# ADC_LED_Monitor.net
KiCad netlist of a schematic drawn in Altium Designer
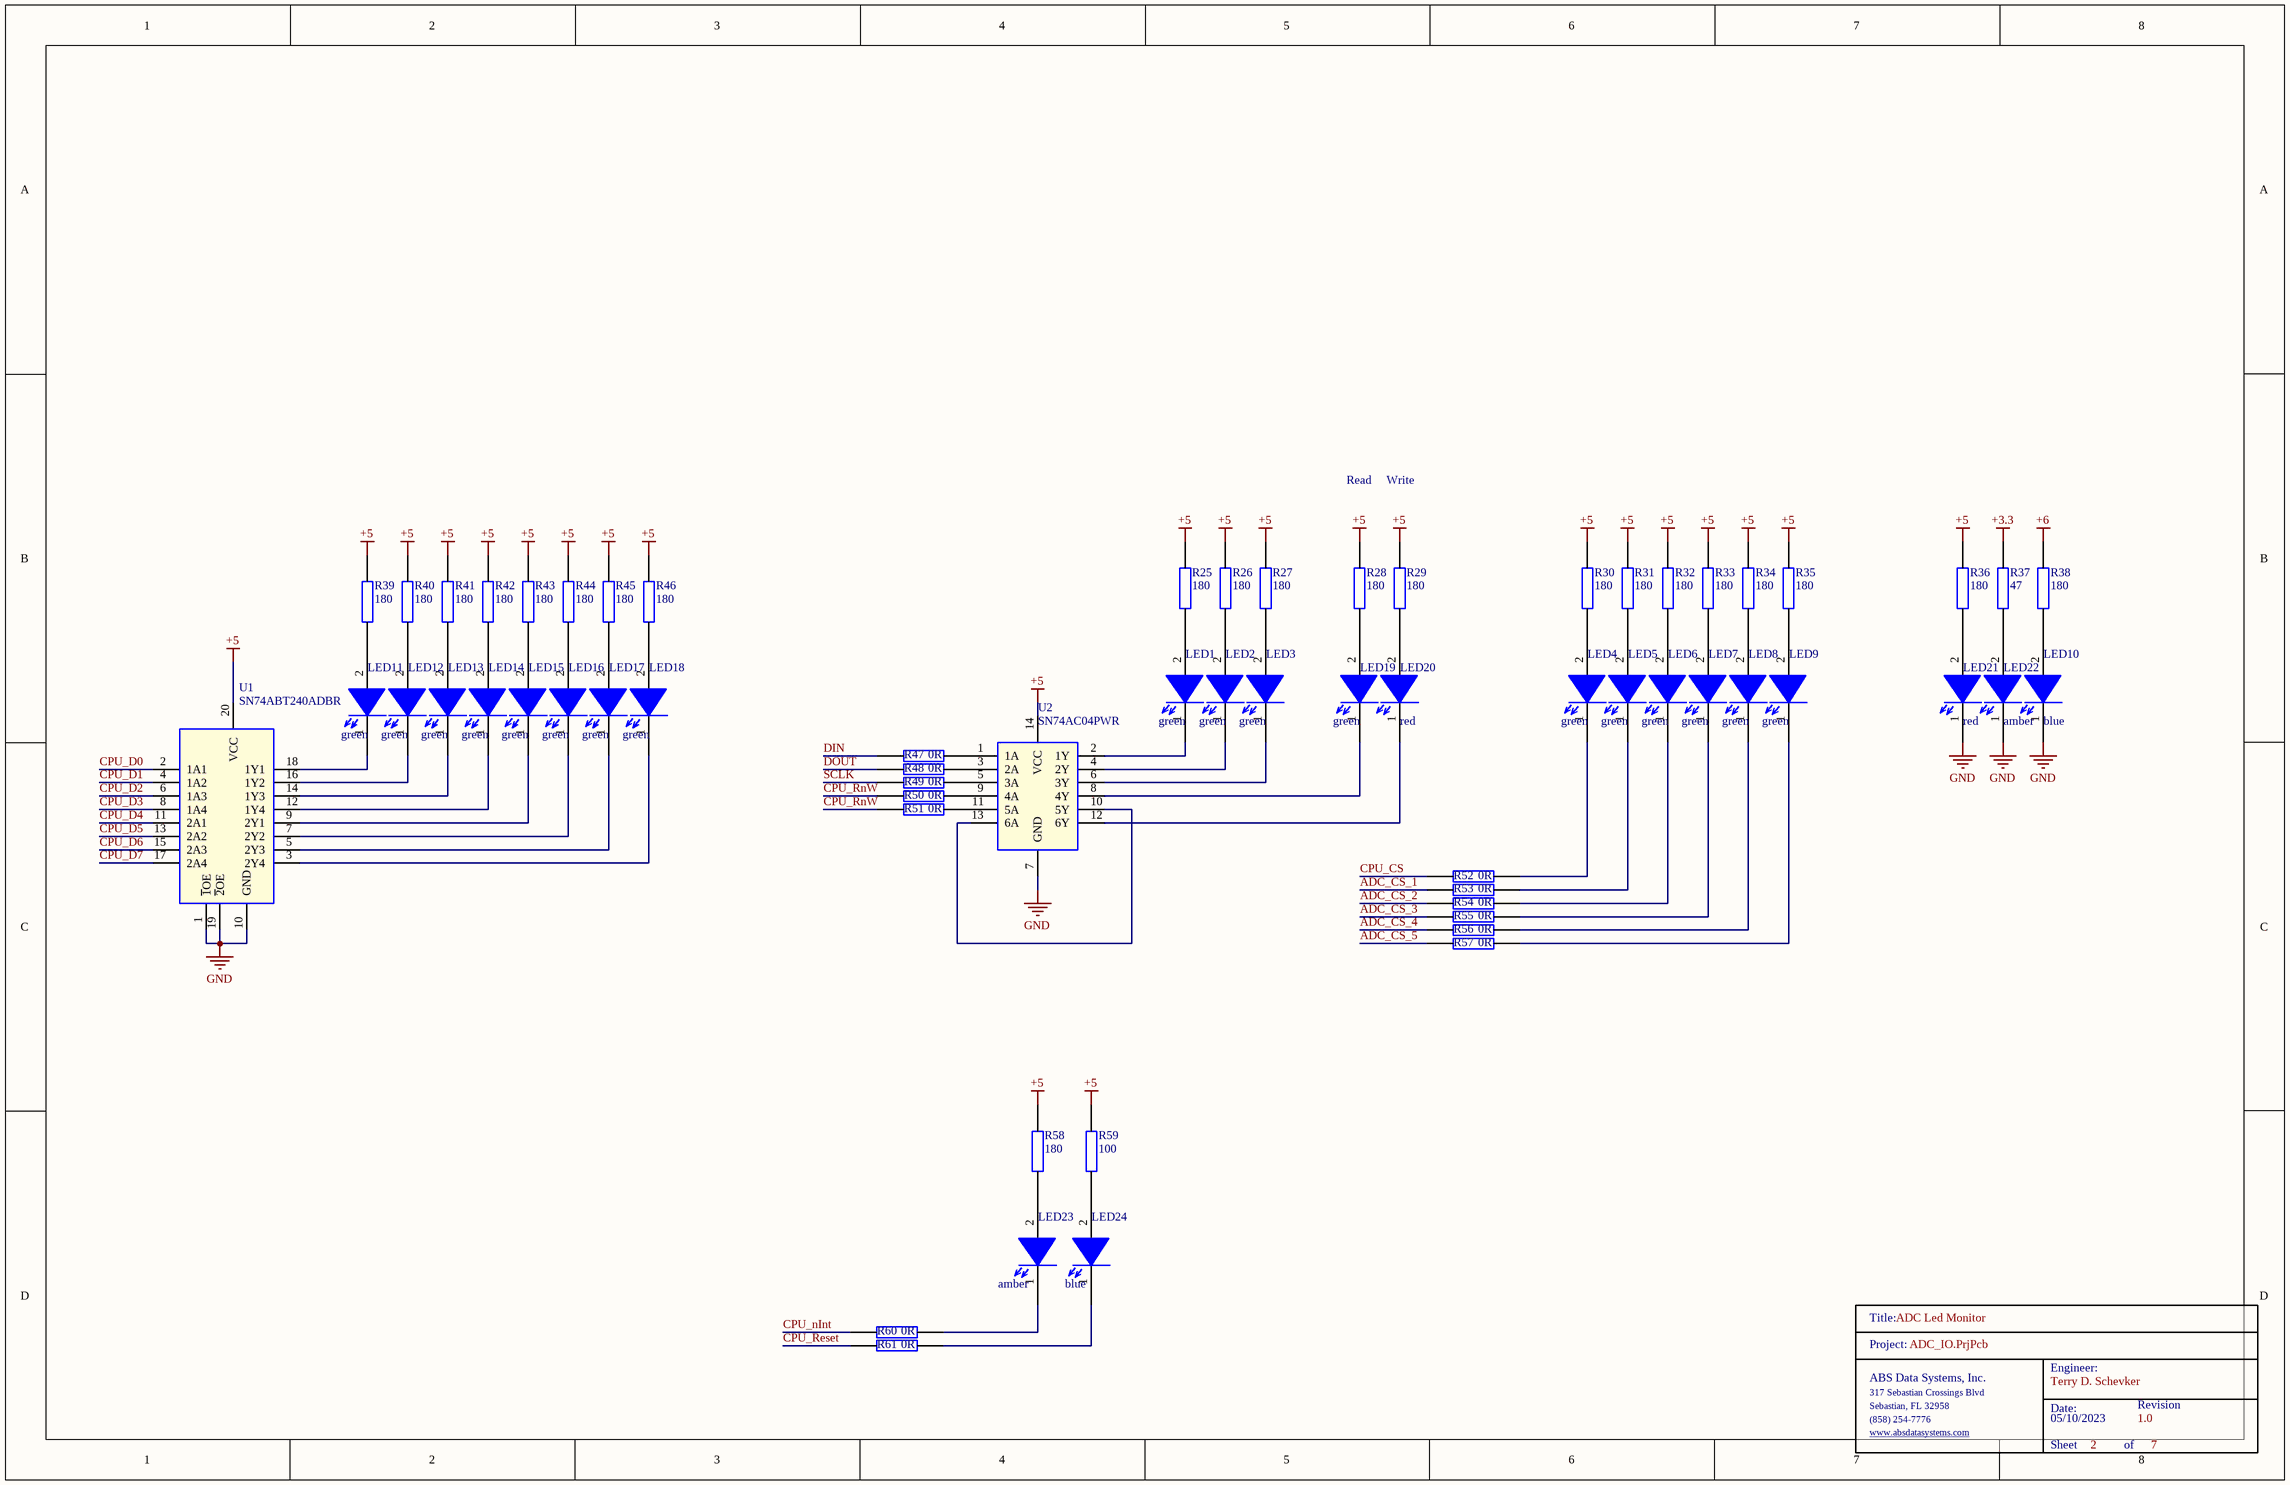
[diagram p0: ADC_LED_Monitor.SchDoc]

(export (version "E")
  (design (tool "Eeschema 10.0.6"))
  (components
    (comp (ref "LED1")
      (value "green")
      (footprint "0603_Diode")
      (description "Wurth Elektronik 0603 green")
      (fields
        (field (name "MANUFACTURER") "Wurth Electronics")
        (field (name "MANUFACTURER PART NUMBER") "150060GS75000")
      )
      (libsource (lib "Misc") (part "150060GS75000"))
    )
    (comp (ref "LED2")
      (value "green")
      (footprint "0603_Diode")
      (description "Wurth Elektronik 0603 green")
      (fields
        (field (name "MANUFACTURER") "Wurth Electronics")
        (field (name "MANUFACTURER PART NUMBER") "150060GS75000")
      )
      (libsource (lib "Misc") (part "150060GS75000"))
    )
    (comp (ref "LED3")
      (value "green")
      (footprint "0603_Diode")
      (description "Wurth Elektronik 0603 green")
      (fields
        (field (name "MANUFACTURER") "Wurth Electronics")
        (field (name "MANUFACTURER PART NUMBER") "150060GS75000")
      )
      (libsource (lib "Misc") (part "150060GS75000"))
    )
    (comp (ref "LED4")
      (value "green")
      (footprint "0603_Diode")
      (description "Wurth Elektronik 0603 green")
      (fields
        (field (name "MANUFACTURER") "Wurth Electronics")
        (field (name "MANUFACTURER PART NUMBER") "150060GS75000")
      )
      (libsource (lib "Misc") (part "150060GS75000"))
    )
    (comp (ref "LED5")
      (value "green")
      (footprint "0603_Diode")
      (description "Wurth Elektronik 0603 green")
      (fields
        (field (name "MANUFACTURER") "Wurth Electronics")
        (field (name "MANUFACTURER PART NUMBER") "150060GS75000")
      )
      (libsource (lib "Misc") (part "150060GS75000"))
    )
    (comp (ref "LED6")
      (value "green")
      (footprint "0603_Diode")
      (description "Wurth Elektronik 0603 green")
      (fields
        (field (name "MANUFACTURER") "Wurth Electronics")
        (field (name "MANUFACTURER PART NUMBER") "150060GS75000")
      )
      (libsource (lib "Misc") (part "150060GS75000"))
    )
    (comp (ref "LED7")
      (value "green")
      (footprint "0603_Diode")
      (description "Wurth Elektronik 0603 green")
      (fields
        (field (name "MANUFACTURER") "Wurth Electronics")
        (field (name "MANUFACTURER PART NUMBER") "150060GS75000")
      )
      (libsource (lib "Misc") (part "150060GS75000"))
    )
    (comp (ref "LED8")
      (value "green")
      (footprint "0603_Diode")
      (description "Wurth Elektronik 0603 green")
      (fields
        (field (name "MANUFACTURER") "Wurth Electronics")
        (field (name "MANUFACTURER PART NUMBER") "150060GS75000")
      )
      (libsource (lib "Misc") (part "150060GS75000"))
    )
    (comp (ref "LED9")
      (value "green")
      (footprint "0603_Diode")
      (description "Wurth Elektronik 0603 green")
      (fields
        (field (name "MANUFACTURER") "Wurth Electronics")
        (field (name "MANUFACTURER PART NUMBER") "150060GS75000")
      )
      (libsource (lib "Misc") (part "150060GS75000"))
    )
    (comp (ref "LED10")
      (value "blue")
      (footprint "0603_Diode")
      (description "Wurth Elektronik 0603 blue")
      (fields
        (field (name "MANUFACTURER") "Wurth Electronics")
        (field (name "MANUFACTURER PART NUMBER") "150060GS75000")
      )
      (libsource (lib "Misc") (part "150060BS75000"))
    )
    (comp (ref "LED11")
      (value "green")
      (footprint "0603_Diode")
      (description "Wurth Elektronik 0603 green")
      (fields
        (field (name "MANUFACTURER") "Wurth Electronics")
        (field (name "MANUFACTURER PART NUMBER") "150060GS75000")
      )
      (libsource (lib "Misc") (part "150060GS75000"))
    )
    (comp (ref "LED12")
      (value "green")
      (footprint "0603_Diode")
      (description "Wurth Elektronik 0603 green")
      (fields
        (field (name "MANUFACTURER") "Wurth Electronics")
        (field (name "MANUFACTURER PART NUMBER") "150060GS75000")
      )
      (libsource (lib "Misc") (part "150060GS75000"))
    )
    (comp (ref "LED13")
      (value "green")
      (footprint "0603_Diode")
      (description "Wurth Elektronik 0603 green")
      (fields
        (field (name "MANUFACTURER") "Wurth Electronics")
        (field (name "MANUFACTURER PART NUMBER") "150060GS75000")
      )
      (libsource (lib "Misc") (part "150060GS75000"))
    )
    (comp (ref "LED14")
      (value "green")
      (footprint "0603_Diode")
      (description "Wurth Elektronik 0603 green")
      (fields
        (field (name "MANUFACTURER") "Wurth Electronics")
        (field (name "MANUFACTURER PART NUMBER") "150060GS75000")
      )
      (libsource (lib "Misc") (part "150060GS75000"))
    )
    (comp (ref "LED15")
      (value "green")
      (footprint "0603_Diode")
      (description "Wurth Elektronik 0603 green")
      (fields
        (field (name "MANUFACTURER") "Wurth Electronics")
        (field (name "MANUFACTURER PART NUMBER") "150060GS75000")
      )
      (libsource (lib "Misc") (part "150060GS75000"))
    )
    (comp (ref "LED16")
      (value "green")
      (footprint "0603_Diode")
      (description "Wurth Elektronik 0603 green")
      (fields
        (field (name "MANUFACTURER") "Wurth Electronics")
        (field (name "MANUFACTURER PART NUMBER") "150060GS75000")
      )
      (libsource (lib "Misc") (part "150060GS75000"))
    )
    (comp (ref "LED17")
      (value "green")
      (footprint "0603_Diode")
      (description "Wurth Elektronik 0603 green")
      (fields
        (field (name "MANUFACTURER") "Wurth Electronics")
        (field (name "MANUFACTURER PART NUMBER") "150060GS75000")
      )
      (libsource (lib "Misc") (part "150060GS75000"))
    )
    (comp (ref "LED18")
      (value "green")
      (footprint "0603_Diode")
      (description "Wurth Elektronik 0603 green")
      (fields
        (field (name "MANUFACTURER") "Wurth Electronics")
        (field (name "MANUFACTURER PART NUMBER") "150060GS75000")
      )
      (libsource (lib "Misc") (part "150060GS75000"))
    )
    (comp (ref "LED19")
      (value "green")
      (footprint "0603_Diode")
      (description "Wurth Elektronik 0603 green")
      (fields
        (field (name "MANUFACTURER") "Wurth Electronics")
        (field (name "MANUFACTURER PART NUMBER") "150060GS75000")
      )
      (libsource (lib "Misc") (part "150060GS75000"))
    )
    (comp (ref "LED20")
      (value "red")
      (footprint "0603_Diode")
      (description "Wurth Elektronik 0603 red")
      (fields
        (field (name "MANUFACTURER") "Wurth Electronics")
        (field (name "MANUFACTURER PART NUMBER") "150060GS75000")
      )
      (libsource (lib "Misc") (part "150060RS75000"))
    )
    (comp (ref "LED21")
      (value "red")
      (footprint "0603_Diode")
      (description "Wurth Elektronik 0603 red")
      (fields
        (field (name "MANUFACTURER") "Wurth Electronics")
        (field (name "MANUFACTURER PART NUMBER") "150060GS75000")
      )
      (libsource (lib "Misc") (part "150060RS75000"))
    )
    (comp (ref "LED22")
      (value "amber")
      (footprint "0603_Diode")
      (description "Wurth Elektronik 0603 amber")
      (fields
        (field (name "MANUFACTURER") "Wurth Electronics")
        (field (name "MANUFACTURER PART NUMBER") "150060GS75000")
      )
      (libsource (lib "Misc") (part "150060AS75000"))
    )
    (comp (ref "LED23")
      (value "amber")
      (footprint "0603_Diode")
      (description "Wurth Elektronik 0603 amber")
      (fields
        (field (name "MANUFACTURER") "Wurth Electronics")
        (field (name "MANUFACTURER PART NUMBER") "150060GS75000")
      )
      (libsource (lib "Misc") (part "150060AS75000"))
    )
    (comp (ref "LED24")
      (value "blue")
      (footprint "0603_Diode")
      (description "Wurth Elektronik 0603 blue")
      (fields
        (field (name "MANUFACTURER") "Wurth Electronics")
        (field (name "MANUFACTURER PART NUMBER") "150060GS75000")
      )
      (libsource (lib "Misc") (part "150060BS75000"))
    )
    (comp (ref "R25")
      (value "180")
      (footprint "0603")
      (description "YAGEO 0603 180 ohm")
      (fields
        (field (name "MOUSER PART NUMBER") "603-RC0603JR-070RL")
        (field (name "MANUFACTURER_PART_NUMBER") "RC0603JR-070RL")
      )
      (libsource (lib "Resistors") (part "RC0603FR-13180RL"))
    )
    (comp (ref "R26")
      (value "180")
      (footprint "0603")
      (description "YAGEO 0603 180 ohm")
      (fields
        (field (name "MOUSER PART NUMBER") "603-RC0603JR-070RL")
        (field (name "MANUFACTURER_PART_NUMBER") "RC0603JR-070RL")
      )
      (libsource (lib "Resistors") (part "RC0603FR-13180RL"))
    )
    (comp (ref "R27")
      (value "180")
      (footprint "0603")
      (description "YAGEO 0603 180 ohm")
      (fields
        (field (name "MOUSER PART NUMBER") "603-RC0603JR-070RL")
        (field (name "MANUFACTURER_PART_NUMBER") "RC0603JR-070RL")
      )
      (libsource (lib "Resistors") (part "RC0603FR-13180RL"))
    )
    (comp (ref "R28")
      (value "180")
      (footprint "0603")
      (description "YAGEO 0603 180 ohm")
      (fields
        (field (name "MOUSER PART NUMBER") "603-RC0603JR-070RL")
        (field (name "MANUFACTURER_PART_NUMBER") "RC0603JR-070RL")
      )
      (libsource (lib "Resistors") (part "RC0603FR-13180RL"))
    )
    (comp (ref "R29")
      (value "180")
      (footprint "0603")
      (description "YAGEO 0603 180 ohm")
      (fields
        (field (name "MOUSER PART NUMBER") "603-RC0603JR-070RL")
        (field (name "MANUFACTURER_PART_NUMBER") "RC0603JR-070RL")
      )
      (libsource (lib "Resistors") (part "RC0603FR-13180RL"))
    )
    (comp (ref "R30")
      (value "180")
      (footprint "0603")
      (description "YAGEO 0603 180 ohm")
      (fields
        (field (name "MOUSER PART NUMBER") "603-RC0603JR-070RL")
        (field (name "MANUFACTURER_PART_NUMBER") "RC0603JR-070RL")
      )
      (libsource (lib "Resistors") (part "RC0603FR-13180RL"))
    )
    (comp (ref "R31")
      (value "180")
      (footprint "0603")
      (description "YAGEO 0603 180 ohm")
      (fields
        (field (name "MOUSER PART NUMBER") "603-RC0603JR-070RL")
        (field (name "MANUFACTURER_PART_NUMBER") "RC0603JR-070RL")
      )
      (libsource (lib "Resistors") (part "RC0603FR-13180RL"))
    )
    (comp (ref "R32")
      (value "180")
      (footprint "0603")
      (description "YAGEO 0603 180 ohm")
      (fields
        (field (name "MOUSER PART NUMBER") "603-RC0603JR-070RL")
        (field (name "MANUFACTURER_PART_NUMBER") "RC0603JR-070RL")
      )
      (libsource (lib "Resistors") (part "RC0603FR-13180RL"))
    )
    (comp (ref "R33")
      (value "180")
      (footprint "0603")
      (description "YAGEO 0603 180 ohm")
      (fields
        (field (name "MOUSER PART NUMBER") "603-RC0603JR-070RL")
        (field (name "MANUFACTURER_PART_NUMBER") "RC0603JR-070RL")
      )
      (libsource (lib "Resistors") (part "RC0603FR-13180RL"))
    )
    (comp (ref "R34")
      (value "180")
      (footprint "0603")
      (description "YAGEO 0603 180 ohm")
      (fields
        (field (name "MOUSER PART NUMBER") "603-RC0603JR-070RL")
        (field (name "MANUFACTURER_PART_NUMBER") "RC0603JR-070RL")
      )
      (libsource (lib "Resistors") (part "RC0603FR-13180RL"))
    )
    (comp (ref "R35")
      (value "180")
      (footprint "0603")
      (description "YAGEO 0603 180 ohm")
      (fields
        (field (name "MOUSER PART NUMBER") "603-RC0603JR-070RL")
        (field (name "MANUFACTURER_PART_NUMBER") "RC0603JR-070RL")
      )
      (libsource (lib "Resistors") (part "RC0603FR-13180RL"))
    )
    (comp (ref "R36")
      (value "180")
      (footprint "0603")
      (description "YAGEO 0603 180 ohm")
      (fields
        (field (name "MOUSER PART NUMBER") "603-RC0603JR-070RL")
        (field (name "MANUFACTURER_PART_NUMBER") "RC0603JR-070RL")
      )
      (libsource (lib "Resistors") (part "RC0603FR-13180RL"))
    )
    (comp (ref "R37")
      (value "47")
      (footprint "0603")
      (description "YAGEO 0603 47")
      (fields
        (field (name "MOUSER PART NUMBER") "603-RC0603JR-070RL")
        (field (name "MANUFACTURER_PART_NUMBER") "RC0603JR-070RL")
      )
      (libsource (lib "Resistors") (part "RC0603FR-0747KL"))
    )
    (comp (ref "R38")
      (value "180")
      (footprint "0603")
      (description "YAGEO 0603 180 ohm")
      (fields
        (field (name "MOUSER PART NUMBER") "603-RC0603JR-070RL")
        (field (name "MANUFACTURER_PART_NUMBER") "RC0603JR-070RL")
      )
      (libsource (lib "Resistors") (part "RC0603FR-13180RL"))
    )
    (comp (ref "R39")
      (value "180")
      (footprint "0603")
      (description "YAGEO 0603 180 ohm")
      (fields
        (field (name "MOUSER PART NUMBER") "603-RC0603JR-070RL")
        (field (name "MANUFACTURER_PART_NUMBER") "RC0603JR-070RL")
      )
      (libsource (lib "Resistors") (part "RC0603FR-13180RL"))
    )
    (comp (ref "R40")
      (value "180")
      (footprint "0603")
      (description "YAGEO 0603 180 ohm")
      (fields
        (field (name "MOUSER PART NUMBER") "603-RC0603JR-070RL")
        (field (name "MANUFACTURER_PART_NUMBER") "RC0603JR-070RL")
      )
      (libsource (lib "Resistors") (part "RC0603FR-13180RL"))
    )
    (comp (ref "R41")
      (value "180")
      (footprint "0603")
      (description "YAGEO 0603 180 ohm")
      (fields
        (field (name "MOUSER PART NUMBER") "603-RC0603JR-070RL")
        (field (name "MANUFACTURER_PART_NUMBER") "RC0603JR-070RL")
      )
      (libsource (lib "Resistors") (part "RC0603FR-13180RL"))
    )
    (comp (ref "R42")
      (value "180")
      (footprint "0603")
      (description "YAGEO 0603 180 ohm")
      (fields
        (field (name "MOUSER PART NUMBER") "603-RC0603JR-070RL")
        (field (name "MANUFACTURER_PART_NUMBER") "RC0603JR-070RL")
      )
      (libsource (lib "Resistors") (part "RC0603FR-13180RL"))
    )
    (comp (ref "R43")
      (value "180")
      (footprint "0603")
      (description "YAGEO 0603 180 ohm")
      (fields
        (field (name "MOUSER PART NUMBER") "603-RC0603JR-070RL")
        (field (name "MANUFACTURER_PART_NUMBER") "RC0603JR-070RL")
      )
      (libsource (lib "Resistors") (part "RC0603FR-13180RL"))
    )
    (comp (ref "R44")
      (value "180")
      (footprint "0603")
      (description "YAGEO 0603 180 ohm")
      (fields
        (field (name "MOUSER PART NUMBER") "603-RC0603JR-070RL")
        (field (name "MANUFACTURER_PART_NUMBER") "RC0603JR-070RL")
      )
      (libsource (lib "Resistors") (part "RC0603FR-13180RL"))
    )
    (comp (ref "R45")
      (value "180")
      (footprint "0603")
      (description "YAGEO 0603 180 ohm")
      (fields
        (field (name "MOUSER PART NUMBER") "603-RC0603JR-070RL")
        (field (name "MANUFACTURER_PART_NUMBER") "RC0603JR-070RL")
      )
      (libsource (lib "Resistors") (part "RC0603FR-13180RL"))
    )
    (comp (ref "R46")
      (value "180")
      (footprint "0603")
      (description "YAGEO 0603 180 ohm")
      (fields
        (field (name "MOUSER PART NUMBER") "603-RC0603JR-070RL")
        (field (name "MANUFACTURER_PART_NUMBER") "RC0603JR-070RL")
      )
      (libsource (lib "Resistors") (part "RC0603FR-13180RL"))
    )
    (comp (ref "R47")
      (value "0R")
      (footprint "0603")
      (description "YAGEO 0603 0 ohm")
      (fields
        (field (name "MOUSER PART NUMBER") "603-RC0603JR-070RL")
        (field (name "MANUFACTURER_PART_NUMBER") "RC0603JR-070RL")
      )
      (libsource (lib "Resistors") (part "RC0603JR-070RL"))
    )
    (comp (ref "R48")
      (value "0R")
      (footprint "0603")
      (description "YAGEO 0603 0 ohm")
      (fields
        (field (name "MOUSER PART NUMBER") "603-RC0603JR-070RL")
        (field (name "MANUFACTURER_PART_NUMBER") "RC0603JR-070RL")
      )
      (libsource (lib "Resistors") (part "RC0603JR-070RL"))
    )
    (comp (ref "R49")
      (value "0R")
      (footprint "0603")
      (description "YAGEO 0603 0 ohm")
      (fields
        (field (name "MOUSER PART NUMBER") "603-RC0603JR-070RL")
        (field (name "MANUFACTURER_PART_NUMBER") "RC0603JR-070RL")
      )
      (libsource (lib "Resistors") (part "RC0603JR-070RL"))
    )
    (comp (ref "R50")
      (value "0R")
      (footprint "0603")
      (description "YAGEO 0603 0 ohm")
      (fields
        (field (name "MOUSER PART NUMBER") "603-RC0603JR-070RL")
        (field (name "MANUFACTURER_PART_NUMBER") "RC0603JR-070RL")
      )
      (libsource (lib "Resistors") (part "RC0603JR-070RL"))
    )
    (comp (ref "R51")
      (value "0R")
      (footprint "0603")
      (description "YAGEO 0603 0 ohm")
      (fields
        (field (name "MOUSER PART NUMBER") "603-RC0603JR-070RL")
        (field (name "MANUFACTURER_PART_NUMBER") "RC0603JR-070RL")
      )
      (libsource (lib "Resistors") (part "RC0603JR-070RL"))
    )
    (comp (ref "R52")
      (value "0R")
      (footprint "0603")
      (description "YAGEO 0603 0 ohm")
      (fields
        (field (name "MOUSER PART NUMBER") "603-RC0603JR-070RL")
        (field (name "MANUFACTURER_PART_NUMBER") "RC0603JR-070RL")
      )
      (libsource (lib "Resistors") (part "RC0603JR-070RL"))
    )
    (comp (ref "R53")
      (value "0R")
      (footprint "0603")
      (description "YAGEO 0603 0 ohm")
      (fields
        (field (name "MOUSER PART NUMBER") "603-RC0603JR-070RL")
        (field (name "MANUFACTURER_PART_NUMBER") "RC0603JR-070RL")
      )
      (libsource (lib "Resistors") (part "RC0603JR-070RL"))
    )
    (comp (ref "R54")
      (value "0R")
      (footprint "0603")
      (description "YAGEO 0603 0 ohm")
      (fields
        (field (name "MOUSER PART NUMBER") "603-RC0603JR-070RL")
        (field (name "MANUFACTURER_PART_NUMBER") "RC0603JR-070RL")
      )
      (libsource (lib "Resistors") (part "RC0603JR-070RL"))
    )
    (comp (ref "R55")
      (value "0R")
      (footprint "0603")
      (description "YAGEO 0603 0 ohm")
      (fields
        (field (name "MOUSER PART NUMBER") "603-RC0603JR-070RL")
        (field (name "MANUFACTURER_PART_NUMBER") "RC0603JR-070RL")
      )
      (libsource (lib "Resistors") (part "RC0603JR-070RL"))
    )
    (comp (ref "R56")
      (value "0R")
      (footprint "0603")
      (description "YAGEO 0603 0 ohm")
      (fields
        (field (name "MOUSER PART NUMBER") "603-RC0603JR-070RL")
        (field (name "MANUFACTURER_PART_NUMBER") "RC0603JR-070RL")
      )
      (libsource (lib "Resistors") (part "RC0603JR-070RL"))
    )
    (comp (ref "R57")
      (value "0R")
      (footprint "0603")
      (description "YAGEO 0603 0 ohm")
      (fields
        (field (name "MOUSER PART NUMBER") "603-RC0603JR-070RL")
        (field (name "MANUFACTURER_PART_NUMBER") "RC0603JR-070RL")
      )
      (libsource (lib "Resistors") (part "RC0603JR-070RL"))
    )
    (comp (ref "R58")
      (value "180")
      (footprint "0603")
      (description "YAGEO 0603 180 ohm")
      (fields
        (field (name "MOUSER PART NUMBER") "603-RC0603JR-070RL")
        (field (name "MANUFACTURER_PART_NUMBER") "RC0603JR-070RL")
      )
      (libsource (lib "Resistors") (part "RC0603FR-13180RL"))
    )
    (comp (ref "R59")
      (value "100")
      (footprint "0603")
      (description "YAGEO 0603 100 ohm")
      (fields
        (field (name "MOUSER PART NUMBER") "603-RC0603JR-070RL")
        (field (name "MANUFACTURER_PART_NUMBER") "RC0603JR-070RL")
      )
      (libsource (lib "Resistors") (part "RC0603FR-10100RL"))
    )
    (comp (ref "R60")
      (value "0R")
      (footprint "0603")
      (description "YAGEO 0603 0 ohm")
      (fields
        (field (name "MOUSER PART NUMBER") "603-RC0603JR-070RL")
        (field (name "MANUFACTURER_PART_NUMBER") "RC0603JR-070RL")
      )
      (libsource (lib "Resistors") (part "RC0603JR-070RL"))
    )
    (comp (ref "R61")
      (value "0R")
      (footprint "0603")
      (description "YAGEO 0603 0 ohm")
      (fields
        (field (name "MOUSER PART NUMBER") "603-RC0603JR-070RL")
        (field (name "MANUFACTURER_PART_NUMBER") "RC0603JR-070RL")
      )
      (libsource (lib "Resistors") (part "RC0603JR-070RL"))
    )
    (comp (ref "TitleBlock_2") (value "TitleBlock") (libsource (lib "Misc") (part "TitleBlock")))
    (comp (ref "U1")
      (value "SN74ABT240ADBR")
      (footprint "SOP65P780X200-20N")
      (description "Octal Buffers/Drivers With 3-State Outputs")
      (fields (field (name "MOUSER PART NUMBER") "595-SN74ABT240ADBR"))
      (libsource (lib "Logic") (part "SN74ABT240ADBR"))
    )
    (comp (ref "U2")
      (value "SN74AC04PWR")
      (footprint "SOP65P640X120-14N")
      (description "Hex Inverters")
      (fields (field (name "MOUSER PART NUMBER") "595-SN74AC04PWR"))
      (libsource (lib "Logic") (part "SN74AC04PWR"))
    )
  )
  (nets
    (net (code "1") (name "+3.3") (class "Default")
      (node (ref "R37") (pin "1") (pinfunction "1_1") (pintype "passive"))
    )
    (net (code "2") (name "+5") (class "Default")
      (node (ref "R25") (pin "2") (pinfunction "2_2") (pintype "passive"))
      (node (ref "R26") (pin "2") (pinfunction "2_2") (pintype "passive"))
      (node (ref "R27") (pin "2") (pinfunction "2_2") (pintype "passive"))
      (node (ref "R28") (pin "2") (pinfunction "2_2") (pintype "passive"))
      (node (ref "R29") (pin "2") (pinfunction "2_2") (pintype "passive"))
      (node (ref "R30") (pin "2") (pinfunction "2_2") (pintype "passive"))
      (node (ref "R31") (pin "2") (pinfunction "2_2") (pintype "passive"))
      (node (ref "R32") (pin "2") (pinfunction "2_2") (pintype "passive"))
      (node (ref "R33") (pin "2") (pinfunction "2_2") (pintype "passive"))
      (node (ref "R34") (pin "2") (pinfunction "2_2") (pintype "passive"))
      (node (ref "R35") (pin "2") (pinfunction "2_2") (pintype "passive"))
      (node (ref "R36") (pin "2") (pinfunction "2_2") (pintype "passive"))
      (node (ref "R39") (pin "2") (pinfunction "2_2") (pintype "passive"))
      (node (ref "R40") (pin "2") (pinfunction "2_2") (pintype "passive"))
      (node (ref "R41") (pin "2") (pinfunction "2_2") (pintype "passive"))
      (node (ref "R42") (pin "2") (pinfunction "2_2") (pintype "passive"))
      (node (ref "R43") (pin "2") (pinfunction "2_2") (pintype "passive"))
      (node (ref "R44") (pin "2") (pinfunction "2_2") (pintype "passive"))
      (node (ref "R45") (pin "2") (pinfunction "2_2") (pintype "passive"))
      (node (ref "R46") (pin "2") (pinfunction "2_2") (pintype "passive"))
      (node (ref "R58") (pin "2") (pinfunction "2_2") (pintype "passive"))
      (node (ref "R59") (pin "1") (pinfunction "1_1") (pintype "passive"))
      (node (ref "U1") (pin "20") (pinfunction "VCC_20") (pintype "passive"))
      (node (ref "U2") (pin "14") (pinfunction "VCC_14") (pintype "passive"))
    )
    (net (code "3") (name "+6") (class "Default")
      (node (ref "R38") (pin "2") (pinfunction "2_2") (pintype "passive"))
    )
    (net (code "4") (name "/ADC_CS_1") (class "Default")
      (node (ref "R53") (pin "1") (pinfunction "1_1") (pintype "passive"))
    )
    (net (code "5") (name "/ADC_CS_2") (class "Default")
      (node (ref "R54") (pin "1") (pinfunction "1_1") (pintype "passive"))
    )
    (net (code "6") (name "/ADC_CS_3") (class "Default")
      (node (ref "R55") (pin "1") (pinfunction "1_1") (pintype "passive"))
    )
    (net (code "7") (name "/ADC_CS_4") (class "Default")
      (node (ref "R56") (pin "1") (pinfunction "1_1") (pintype "passive"))
    )
    (net (code "8") (name "/ADC_CS_5") (class "Default")
      (node (ref "R57") (pin "1") (pinfunction "1_1") (pintype "passive"))
    )
    (net (code "9") (name "/CPU_CS") (class "Default")
      (node (ref "R52") (pin "1") (pinfunction "1_1") (pintype "passive"))
    )
    (net (code "10") (name "/CPU_D0") (class "Default")
      (node (ref "U1") (pin "2") (pinfunction "1A1_2") (pintype "passive"))
    )
    (net (code "11") (name "/CPU_D1") (class "Default")
      (node (ref "U1") (pin "4") (pinfunction "1A2_4") (pintype "passive"))
    )
    (net (code "12") (name "/CPU_D2") (class "Default")
      (node (ref "U1") (pin "6") (pinfunction "1A3_6") (pintype "passive"))
    )
    (net (code "13") (name "/CPU_D3") (class "Default")
      (node (ref "U1") (pin "8") (pinfunction "1A4_8") (pintype "passive"))
    )
    (net (code "14") (name "/CPU_D4") (class "Default")
      (node (ref "U1") (pin "11") (pinfunction "2A1_11") (pintype "passive"))
    )
    (net (code "15") (name "/CPU_D5") (class "Default")
      (node (ref "U1") (pin "13") (pinfunction "2A2_13") (pintype "passive"))
    )
    (net (code "16") (name "/CPU_D6") (class "Default")
      (node (ref "U1") (pin "15") (pinfunction "2A3_15") (pintype "passive"))
    )
    (net (code "17") (name "/CPU_D7") (class "Default")
      (node (ref "U1") (pin "17") (pinfunction "2A4_17") (pintype "passive"))
    )
    (net (code "18") (name "/CPU_Reset") (class "Default")
      (node (ref "R61") (pin "1") (pinfunction "1_1") (pintype "passive"))
    )
    (net (code "19") (name "/CPU_RnW") (class "Default")
      (node (ref "R50") (pin "1") (pinfunction "1_1") (pintype "passive"))
      (node (ref "R51") (pin "1") (pinfunction "1_1") (pintype "passive"))
    )
    (net (code "20") (name "/CPU_nInt") (class "Default")
      (node (ref "R60") (pin "1") (pinfunction "1_1") (pintype "passive"))
    )
    (net (code "21") (name "/DIN") (class "Default")
      (node (ref "R47") (pin "1") (pinfunction "1_1") (pintype "passive"))
    )
    (net (code "22") (name "/DOUT") (class "Default")
      (node (ref "R48") (pin "1") (pinfunction "1_1") (pintype "passive"))
    )
    (net (code "23") (name "/SCLK") (class "Default")
      (node (ref "R49") (pin "1") (pinfunction "1_1") (pintype "passive"))
    )
    (net (code "24") (name "GND") (class "Default")
      (node (ref "LED10") (pin "1") (pinfunction "K_1") (pintype "passive"))
      (node (ref "LED21") (pin "1") (pinfunction "K_1") (pintype "passive"))
      (node (ref "LED22") (pin "1") (pinfunction "K_1") (pintype "passive"))
      (node (ref "U1") (pin "1") (pinfunction "~{1}OE_1") (pintype "passive"))
      (node (ref "U1") (pin "10") (pinfunction "GND_10") (pintype "passive"))
      (node (ref "U1") (pin "19") (pinfunction "~{2}OE_19") (pintype "passive"))
      (node (ref "U2") (pin "7") (pinfunction "GND_7") (pintype "passive"))
    )
    (net (code "25") (name "Net-(LED1-A)") (class "Default")
      (node (ref "LED1") (pin "2") (pinfunction "A_2") (pintype "passive"))
      (node (ref "R25") (pin "1") (pinfunction "1_1") (pintype "passive"))
    )
    (net (code "26") (name "Net-(LED1-K)") (class "Default")
      (node (ref "LED1") (pin "1") (pinfunction "K_1") (pintype "passive"))
      (node (ref "U2") (pin "2") (pinfunction "1Y_2") (pintype "passive"))
    )
    (net (code "27") (name "Net-(LED2-A)") (class "Default")
      (node (ref "LED2") (pin "2") (pinfunction "A_2") (pintype "passive"))
      (node (ref "R26") (pin "1") (pinfunction "1_1") (pintype "passive"))
    )
    (net (code "28") (name "Net-(LED2-K)") (class "Default")
      (node (ref "LED2") (pin "1") (pinfunction "K_1") (pintype "passive"))
      (node (ref "U2") (pin "4") (pinfunction "2Y_4") (pintype "passive"))
    )
    (net (code "29") (name "Net-(LED3-A)") (class "Default")
      (node (ref "LED3") (pin "2") (pinfunction "A_2") (pintype "passive"))
      (node (ref "R27") (pin "1") (pinfunction "1_1") (pintype "passive"))
    )
    (net (code "30") (name "Net-(LED3-K)") (class "Default")
      (node (ref "LED3") (pin "1") (pinfunction "K_1") (pintype "passive"))
      (node (ref "U2") (pin "6") (pinfunction "3Y_6") (pintype "passive"))
    )
    (net (code "31") (name "Net-(LED4-A)") (class "Default")
      (node (ref "LED4") (pin "2") (pinfunction "A_2") (pintype "passive"))
      (node (ref "R30") (pin "1") (pinfunction "1_1") (pintype "passive"))
    )
    (net (code "32") (name "Net-(LED4-K)") (class "Default")
      (node (ref "LED4") (pin "1") (pinfunction "K_1") (pintype "passive"))
      (node (ref "R52") (pin "2") (pinfunction "2_2") (pintype "passive"))
    )
    (net (code "33") (name "Net-(LED5-A)") (class "Default")
      (node (ref "LED5") (pin "2") (pinfunction "A_2") (pintype "passive"))
      (node (ref "R31") (pin "1") (pinfunction "1_1") (pintype "passive"))
    )
    (net (code "34") (name "Net-(LED5-K)") (class "Default")
      (node (ref "LED5") (pin "1") (pinfunction "K_1") (pintype "passive"))
      (node (ref "R53") (pin "2") (pinfunction "2_2") (pintype "passive"))
    )
    (net (code "35") (name "Net-(LED6-A)") (class "Default")
      (node (ref "LED6") (pin "2") (pinfunction "A_2") (pintype "passive"))
      (node (ref "R32") (pin "1") (pinfunction "1_1") (pintype "passive"))
    )
    (net (code "36") (name "Net-(LED6-K)") (class "Default")
      (node (ref "LED6") (pin "1") (pinfunction "K_1") (pintype "passive"))
      (node (ref "R54") (pin "2") (pinfunction "2_2") (pintype "passive"))
    )
    (net (code "37") (name "Net-(LED7-A)") (class "Default")
      (node (ref "LED7") (pin "2") (pinfunction "A_2") (pintype "passive"))
      (node (ref "R33") (pin "1") (pinfunction "1_1") (pintype "passive"))
    )
    (net (code "38") (name "Net-(LED7-K)") (class "Default")
      (node (ref "LED7") (pin "1") (pinfunction "K_1") (pintype "passive"))
      (node (ref "R55") (pin "2") (pinfunction "2_2") (pintype "passive"))
    )
    (net (code "39") (name "Net-(LED8-A)") (class "Default")
      (node (ref "LED8") (pin "2") (pinfunction "A_2") (pintype "passive"))
      (node (ref "R34") (pin "1") (pinfunction "1_1") (pintype "passive"))
    )
    (net (code "40") (name "Net-(LED8-K)") (class "Default")
      (node (ref "LED8") (pin "1") (pinfunction "K_1") (pintype "passive"))
      (node (ref "R56") (pin "2") (pinfunction "2_2") (pintype "passive"))
    )
    (net (code "41") (name "Net-(LED9-A)") (class "Default")
      (node (ref "LED9") (pin "2") (pinfunction "A_2") (pintype "passive"))
      (node (ref "R35") (pin "1") (pinfunction "1_1") (pintype "passive"))
    )
    (net (code "42") (name "Net-(LED9-K)") (class "Default")
      (node (ref "LED9") (pin "1") (pinfunction "K_1") (pintype "passive"))
      (node (ref "R57") (pin "2") (pinfunction "2_2") (pintype "passive"))
    )
    (net (code "43") (name "Net-(LED10-A)") (class "Default")
      (node (ref "LED10") (pin "2") (pinfunction "A_2") (pintype "passive"))
      (node (ref "R38") (pin "1") (pinfunction "1_1") (pintype "passive"))
    )
    (net (code "44") (name "Net-(LED11-A)") (class "Default")
      (node (ref "LED11") (pin "2") (pinfunction "A_2") (pintype "passive"))
      (node (ref "R39") (pin "1") (pinfunction "1_1") (pintype "passive"))
    )
    (net (code "45") (name "Net-(LED11-K)") (class "Default")
      (node (ref "LED11") (pin "1") (pinfunction "K_1") (pintype "passive"))
      (node (ref "U1") (pin "18") (pinfunction "1Y1_18") (pintype "passive"))
    )
    (net (code "46") (name "Net-(LED12-A)") (class "Default")
      (node (ref "LED12") (pin "2") (pinfunction "A_2") (pintype "passive"))
      (node (ref "R40") (pin "1") (pinfunction "1_1") (pintype "passive"))
    )
    (net (code "47") (name "Net-(LED12-K)") (class "Default")
      (node (ref "LED12") (pin "1") (pinfunction "K_1") (pintype "passive"))
      (node (ref "U1") (pin "16") (pinfunction "1Y2_16") (pintype "passive"))
    )
    (net (code "48") (name "Net-(LED13-A)") (class "Default")
      (node (ref "LED13") (pin "2") (pinfunction "A_2") (pintype "passive"))
      (node (ref "R41") (pin "1") (pinfunction "1_1") (pintype "passive"))
    )
    (net (code "49") (name "Net-(LED13-K)") (class "Default")
      (node (ref "LED13") (pin "1") (pinfunction "K_1") (pintype "passive"))
      (node (ref "U1") (pin "14") (pinfunction "1Y3_14") (pintype "passive"))
    )
    (net (code "50") (name "Net-(LED14-A)") (class "Default")
      (node (ref "LED14") (pin "2") (pinfunction "A_2") (pintype "passive"))
      (node (ref "R42") (pin "1") (pinfunction "1_1") (pintype "passive"))
    )
    (net (code "51") (name "Net-(LED14-K)") (class "Default")
      (node (ref "LED14") (pin "1") (pinfunction "K_1") (pintype "passive"))
      (node (ref "U1") (pin "12") (pinfunction "1Y4_12") (pintype "passive"))
    )
    (net (code "52") (name "Net-(LED15-A)") (class "Default")
      (node (ref "LED15") (pin "2") (pinfunction "A_2") (pintype "passive"))
      (node (ref "R43") (pin "1") (pinfunction "1_1") (pintype "passive"))
    )
    (net (code "53") (name "Net-(LED15-K)") (class "Default")
      (node (ref "LED15") (pin "1") (pinfunction "K_1") (pintype "passive"))
      (node (ref "U1") (pin "9") (pinfunction "2Y1_9") (pintype "passive"))
    )
    (net (code "54") (name "Net-(LED16-A)") (class "Default")
      (node (ref "LED16") (pin "2") (pinfunction "A_2") (pintype "passive"))
      (node (ref "R44") (pin "1") (pinfunction "1_1") (pintype "passive"))
    )
    (net (code "55") (name "Net-(LED16-K)") (class "Default")
      (node (ref "LED16") (pin "1") (pinfunction "K_1") (pintype "passive"))
      (node (ref "U1") (pin "7") (pinfunction "2Y2_7") (pintype "passive"))
    )
    (net (code "56") (name "Net-(LED17-A)") (class "Default")
      (node (ref "LED17") (pin "2") (pinfunction "A_2") (pintype "passive"))
      (node (ref "R45") (pin "1") (pinfunction "1_1") (pintype "passive"))
    )
    (net (code "57") (name "Net-(LED17-K)") (class "Default")
      (node (ref "LED17") (pin "1") (pinfunction "K_1") (pintype "passive"))
      (node (ref "U1") (pin "5") (pinfunction "2Y3_5") (pintype "passive"))
    )
    (net (code "58") (name "Net-(LED18-A)") (class "Default")
      (node (ref "LED18") (pin "2") (pinfunction "A_2") (pintype "passive"))
      (node (ref "R46") (pin "1") (pinfunction "1_1") (pintype "passive"))
    )
    (net (code "59") (name "Net-(LED18-K)") (class "Default")
      (node (ref "LED18") (pin "1") (pinfunction "K_1") (pintype "passive"))
      (node (ref "U1") (pin "3") (pinfunction "2Y4_3") (pintype "passive"))
    )
    (net (code "60") (name "Net-(LED19-A)") (class "Default")
      (node (ref "LED19") (pin "2") (pinfunction "A_2") (pintype "passive"))
      (node (ref "R28") (pin "1") (pinfunction "1_1") (pintype "passive"))
    )
    (net (code "61") (name "Net-(LED19-K)") (class "Default")
      (node (ref "LED19") (pin "1") (pinfunction "K_1") (pintype "passive"))
      (node (ref "U2") (pin "8") (pinfunction "4Y_8") (pintype "passive"))
    )
    (net (code "62") (name "Net-(LED20-A)") (class "Default")
      (node (ref "LED20") (pin "2") (pinfunction "A_2") (pintype "passive"))
      (node (ref "R29") (pin "1") (pinfunction "1_1") (pintype "passive"))
    )
    (net (code "63") (name "Net-(LED20-K)") (class "Default")
      (node (ref "LED20") (pin "1") (pinfunction "K_1") (pintype "passive"))
      (node (ref "U2") (pin "12") (pinfunction "6Y_12") (pintype "passive"))
    )
    (net (code "64") (name "Net-(LED21-A)") (class "Default")
      (node (ref "LED21") (pin "2") (pinfunction "A_2") (pintype "passive"))
      (node (ref "R36") (pin "1") (pinfunction "1_1") (pintype "passive"))
    )
    (net (code "65") (name "Net-(LED22-A)") (class "Default")
      (node (ref "LED22") (pin "2") (pinfunction "A_2") (pintype "passive"))
      (node (ref "R37") (pin "2") (pinfunction "2_2") (pintype "passive"))
    )
    (net (code "66") (name "Net-(LED23-A)") (class "Default")
      (node (ref "LED23") (pin "2") (pinfunction "A_2") (pintype "passive"))
      (node (ref "R58") (pin "1") (pinfunction "1_1") (pintype "passive"))
    )
    (net (code "67") (name "Net-(LED23-K)") (class "Default")
      (node (ref "LED23") (pin "1") (pinfunction "K_1") (pintype "passive"))
      (node (ref "R60") (pin "2") (pinfunction "2_2") (pintype "passive"))
    )
    (net (code "68") (name "Net-(LED24-A)") (class "Default")
      (node (ref "LED24") (pin "2") (pinfunction "A_2") (pintype "passive"))
      (node (ref "R59") (pin "2") (pinfunction "2_2") (pintype "passive"))
    )
    (net (code "69") (name "Net-(LED24-K)") (class "Default")
      (node (ref "LED24") (pin "1") (pinfunction "K_1") (pintype "passive"))
      (node (ref "R61") (pin "2") (pinfunction "2_2") (pintype "passive"))
    )
    (net (code "70") (name "Net-(U2-1A)") (class "Default")
      (node (ref "R47") (pin "2") (pinfunction "2_2") (pintype "passive"))
      (node (ref "U2") (pin "1") (pinfunction "1A_1") (pintype "passive"))
    )
    (net (code "71") (name "Net-(U2-2A)") (class "Default")
      (node (ref "R48") (pin "2") (pinfunction "2_2") (pintype "passive"))
      (node (ref "U2") (pin "3") (pinfunction "2A_3") (pintype "passive"))
    )
    (net (code "72") (name "Net-(U2-3A)") (class "Default")
      (node (ref "R49") (pin "2") (pinfunction "2_2") (pintype "passive"))
      (node (ref "U2") (pin "5") (pinfunction "3A_5") (pintype "passive"))
    )
    (net (code "73") (name "Net-(U2-4A)") (class "Default")
      (node (ref "R50") (pin "2") (pinfunction "2_2") (pintype "passive"))
      (node (ref "U2") (pin "9") (pinfunction "4A_9") (pintype "passive"))
    )
    (net (code "74") (name "Net-(U2-5A)") (class "Default")
      (node (ref "R51") (pin "2") (pinfunction "2_2") (pintype "passive"))
      (node (ref "U2") (pin "11") (pinfunction "5A_11") (pintype "passive"))
    )
    (net (code "75") (name "Net-(U2-5Y)") (class "Default")
      (node (ref "U2") (pin "10") (pinfunction "5Y_10") (pintype "passive"))
      (node (ref "U2") (pin "13") (pinfunction "6A_13") (pintype "passive"))
    )
  )
)
